# stm32.net
KiCad netlist of a schematic drawn in Altium Designer
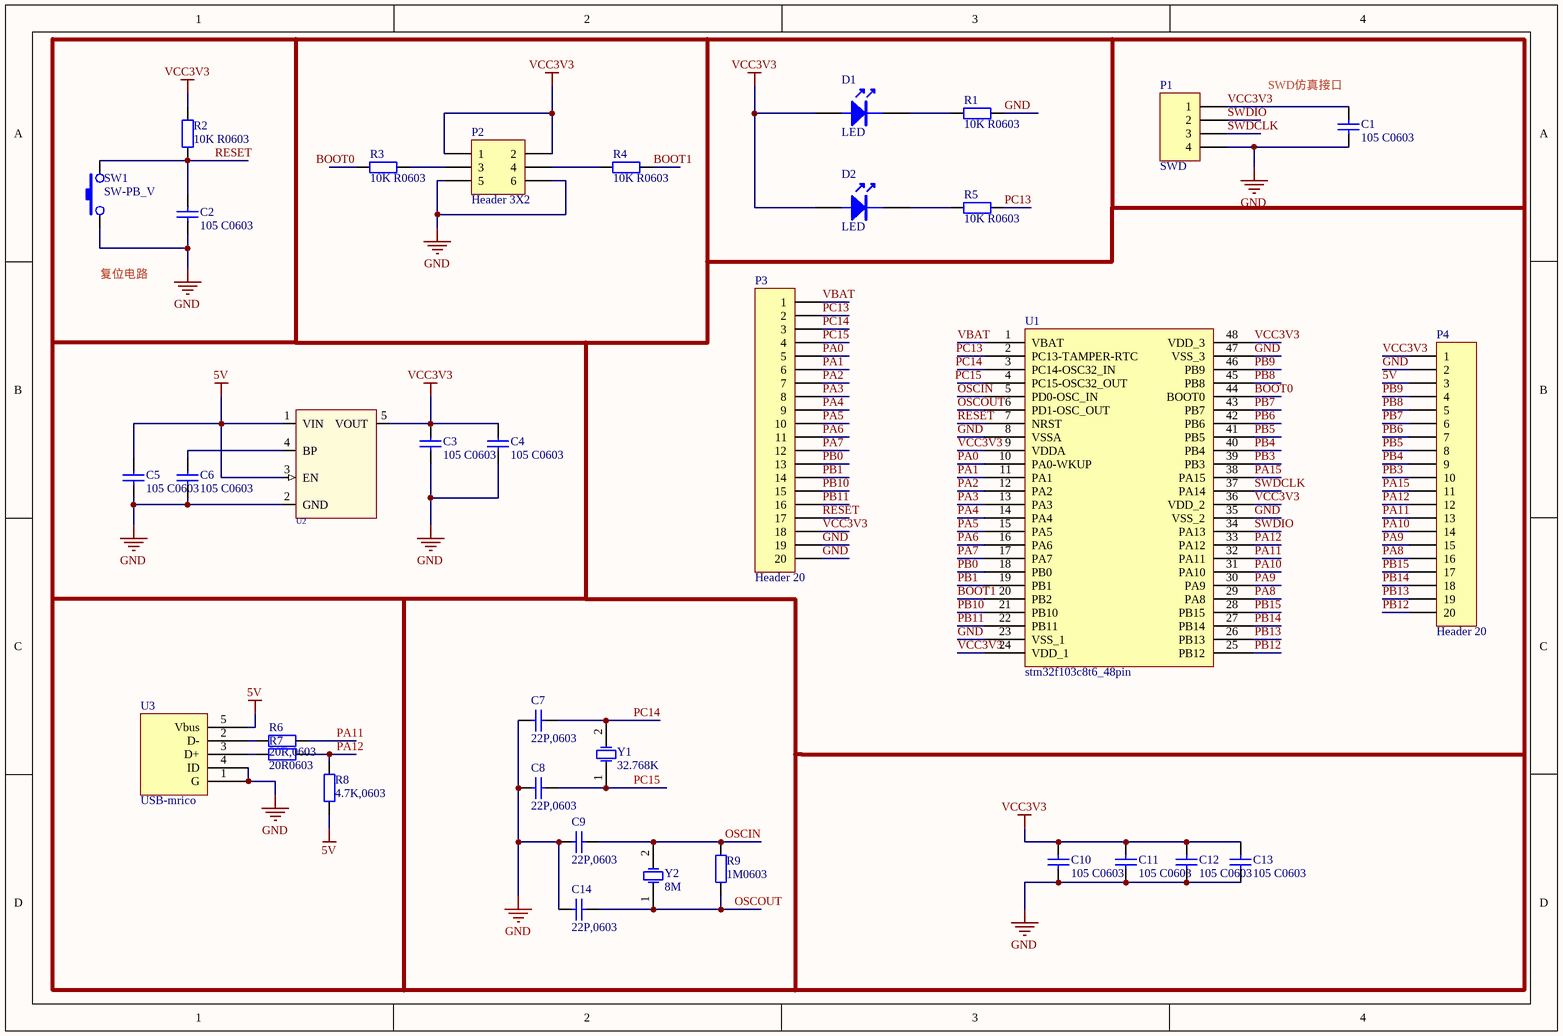
[diagram p0: stm32最小系统.SchDoc]

(export (version "E")
  (design (tool "Eeschema 10.0.6"))
  (components
    (comp (ref "C1")
      (value "105 C0603")
      (footprint "C 0603")
      (fields (field (name "PUBLISHER") "Altium Limited"))
      (libsource (lib "stm32原理图库") (part "Cap"))
    )
    (comp (ref "C2")
      (value "105 C0603")
      (footprint "C 0603")
      (fields (field (name "PUBLISHER") "Altium Limited"))
      (libsource (lib "stm32原理图库") (part "Cap"))
    )
    (comp (ref "C3")
      (value "105 C0603")
      (footprint "C 0603")
      (fields (field (name "PUBLISHER") "Altium Limited"))
      (libsource (lib "stm32原理图库") (part "Cap"))
    )
    (comp (ref "C4")
      (value "105 C0603")
      (footprint "C 0603")
      (fields (field (name "PUBLISHER") "Altium Limited"))
      (libsource (lib "stm32原理图库") (part "Cap"))
    )
    (comp (ref "C5")
      (value "105 C0603")
      (footprint "C 0603")
      (fields (field (name "PUBLISHER") "Altium Limited"))
      (libsource (lib "stm32原理图库") (part "Cap"))
    )
    (comp (ref "C6")
      (value "105 C0603")
      (footprint "C 0603")
      (fields (field (name "PUBLISHER") "Altium Limited"))
      (libsource (lib "stm32原理图库") (part "Cap"))
    )
    (comp (ref "C7")
      (value "22P,0603")
      (footprint "C 0603")
      (description "Capacitor")
      (fields (field (name "PUBLISHER") "Altium Limited"))
      (libsource (lib "STM32F103C8T6") (part "Cap"))
    )
    (comp (ref "C8")
      (value "22P,0603")
      (footprint "C 0603")
      (description "Capacitor")
      (fields (field (name "PUBLISHER") "Altium Limited"))
      (libsource (lib "STM32F103C8T6") (part "Cap"))
    )
    (comp (ref "C9")
      (value "22P,0603")
      (footprint "C 0603")
      (description "Capacitor")
      (fields (field (name "PUBLISHER") "Altium Limited"))
      (libsource (lib "STM32F103C8T6") (part "Cap"))
    )
    (comp (ref "C10")
      (value "105 C0603")
      (footprint "C 0603")
      (fields (field (name "PUBLISHER") "Altium Limited"))
      (libsource (lib "stm32原理图库") (part "Cap"))
    )
    (comp (ref "C11")
      (value "105 C0603")
      (footprint "C 0603")
      (fields (field (name "PUBLISHER") "Altium Limited"))
      (libsource (lib "stm32原理图库") (part "Cap"))
    )
    (comp (ref "C12")
      (value "105 C0603")
      (footprint "C 0603")
      (fields (field (name "PUBLISHER") "Altium Limited"))
      (libsource (lib "stm32原理图库") (part "Cap"))
    )
    (comp (ref "C13")
      (value "105 C0603")
      (footprint "C 0603")
      (fields (field (name "PUBLISHER") "Altium Limited"))
      (libsource (lib "stm32原理图库") (part "Cap"))
    )
    (comp (ref "C14")
      (value "22P,0603")
      (footprint "C 0603")
      (description "Capacitor")
      (fields (field (name "PUBLISHER") "Altium Limited"))
      (libsource (lib "STM32F103C8T6") (part "Cap"))
    )
    (comp (ref "D1") (value "LED") (footprint "LED 0805G") (libsource (lib "stm32原理图库") (part "LED")))
    (comp (ref "D2") (value "LED") (footprint "LED 0805G") (libsource (lib "stm32原理图库") (part "LED")))
    (comp (ref "P1")
      (value "SWD")
      (footprint "HDR-1X4_H")
      (description "Header, 4-Pin")
      (fields (field (name "PUBLISHER") "Altium Limited"))
      (libsource (lib "stm32原理图库") (part "Header 4"))
    )
    (comp (ref "P2")
      (value "Header 3X2")
      (footprint "HDR-3X2")
      (description "Header, 3-Pin, Dual row")
      (fields (field (name "PUBLISHER") "Altium Limited"))
      (libsource (lib "stm32原理图库") (part "Header 3X2"))
    )
    (comp (ref "P3")
      (value "Header 20")
      (footprint "HDR1X20")
      (description "Header, 20-Pin")
      (fields (field (name "PUBLISHER") "Altium Limited"))
      (libsource (lib "stm32原理图库") (part "Header 20"))
    )
    (comp (ref "P4")
      (value "Header 20")
      (footprint "HDR1X20")
      (description "Header, 20-Pin")
      (fields (field (name "PUBLISHER") "Altium Limited"))
      (libsource (lib "") (part "Header 20_1"))
    )
    (comp (ref "R1")
      (value "10K R0603")
      (footprint "R 0603")
      (fields (field (name "PUBLISHER") "Altium Limited"))
      (libsource (lib "stm32原理图库") (part "Res2"))
    )
    (comp (ref "R2")
      (value "10K R0603")
      (footprint "R 0603")
      (fields (field (name "PUBLISHER") "Altium Limited"))
      (libsource (lib "") (part "Res2_1"))
    )
    (comp (ref "R3")
      (value "10K R0603")
      (footprint "R 0603")
      (fields (field (name "PUBLISHER") "Altium Limited"))
      (libsource (lib "stm32原理图库") (part "Res2"))
    )
    (comp (ref "R4")
      (value "10K R0603")
      (footprint "R 0603")
      (fields (field (name "PUBLISHER") "Altium Limited"))
      (libsource (lib "stm32原理图库") (part "Res2"))
    )
    (comp (ref "R5")
      (value "10K R0603")
      (footprint "R 0603")
      (fields (field (name "PUBLISHER") "Altium Limited"))
      (libsource (lib "stm32原理图库") (part "Res2"))
    )
    (comp (ref "R6")
      (value "20R,0603")
      (footprint "R 0603")
      (description "Resistor")
      (fields (field (name "PUBLISHER") "Altium Limited"))
      (libsource (lib "") (part "Res2_1"))
    )
    (comp (ref "R7")
      (value "20R0603")
      (footprint "R 0603")
      (description "Resistor")
      (fields (field (name "PUBLISHER") "Altium Limited"))
      (libsource (lib "") (part "Res2_1"))
    )
    (comp (ref "R8")
      (value "4.7K,0603")
      (footprint "R 0603")
      (description "Resistor")
      (fields (field (name "PUBLISHER") "Altium Limited"))
      (libsource (lib "STM32F103C8T6") (part "Res2"))
    )
    (comp (ref "R9")
      (value "1M0603")
      (footprint "R 0603")
      (description "Resistor")
      (fields (field (name "PUBLISHER") "Altium Limited"))
      (libsource (lib "STM32F103C8T6") (part "Res2"))
    )
    (comp (ref "SW1")
      (value "SW-PB_V")
      (footprint "TSW SMD-3*6*2.5")
      (libsource (lib "stm32原理图库") (part "SW-PB_V"))
    )
    (comp (ref "U1")
      (value "stm32f103c8t6_48pin")
      (footprint "TQFP48 7x7_L")
      (libsource (lib "STM32_Schlib") (part "stm32f103c8t6_48pin"))
    )
    (comp (ref "U2")
      (value "RT9193")
      (footprint "SOT23-5L")
      (fields (field (name "ICA_PARTNUM") "$$2191094$$RT9193-15CU5") (field (name "PART NUMBER") "TMP-13"))
      (libsource (lib "stm32原理图库") (part "RT9193X_5P"))
    )
    (comp (ref "U3")
      (value "USB-mrico")
      (footprint "USB-micro_B")
      (libsource (lib "STM32F103C8T6") (part "usb-STM"))
    )
    (comp (ref "Y1")
      (value "32.768K")
      (footprint "XTAL-49S DIP")
      (description "Crystal Oscillator")
      (fields (field (name "PUBLISHER") "Altium Limited"))
      (libsource (lib "STM32F103C8T6") (part "XTAL"))
    )
    (comp (ref "Y2")
      (value "8M")
      (footprint "XTAL-49S DIP")
      (description "Crystal Oscillator")
      (fields (field (name "PUBLISHER") "Altium Limited"))
      (libsource (lib "STM32F103C8T6") (part "XTAL"))
    )
  )
  (nets
    (net (code "1") (name "/BOOT0") (class "Default")
      (node (ref "R3") (pin "1") (pinfunction "1_1") (pintype "passive"))
      (node (ref "U1") (pin "44") (pinfunction "BOOT0_44") (pintype "passive"))
    )
    (net (code "2") (name "/BOOT1") (class "Default")
      (node (ref "R4") (pin "2") (pinfunction "2_2") (pintype "passive"))
      (node (ref "U1") (pin "20") (pinfunction "PB2_20") (pintype "passive"))
    )
    (net (code "3") (name "/OSCIN") (class "Default")
      (node (ref "C9") (pin "1") (pinfunction "1_1") (pintype "passive"))
      (node (ref "R9") (pin "2") (pinfunction "2_2") (pintype "passive"))
      (node (ref "U1") (pin "5") (pinfunction "PD0-OSC_IN_5") (pintype "passive"))
      (node (ref "Y2") (pin "2") (pinfunction "OSC2_2") (pintype "passive"))
    )
    (net (code "4") (name "/OSCOUT") (class "Default")
      (node (ref "C14") (pin "1") (pinfunction "1_1") (pintype "passive"))
      (node (ref "R9") (pin "1") (pinfunction "1_1") (pintype "passive"))
      (node (ref "U1") (pin "6") (pinfunction "PD1-OSC_OUT_6") (pintype "passive"))
      (node (ref "Y2") (pin "1") (pinfunction "OSC1_1") (pintype "passive"))
    )
    (net (code "5") (name "/PA0") (class "Default")
      (node (ref "P3") (pin "5") (pinfunction "5_5") (pintype "passive"))
      (node (ref "U1") (pin "10") (pinfunction "PA0-WKUP_10") (pintype "passive"))
    )
    (net (code "6") (name "/PA1") (class "Default")
      (node (ref "P3") (pin "6") (pinfunction "6_6") (pintype "passive"))
      (node (ref "U1") (pin "11") (pinfunction "PA1_11") (pintype "passive"))
    )
    (net (code "7") (name "/PA2") (class "Default")
      (node (ref "P3") (pin "7") (pinfunction "7_7") (pintype "passive"))
      (node (ref "U1") (pin "12") (pinfunction "PA2_12") (pintype "passive"))
    )
    (net (code "8") (name "/PA3") (class "Default")
      (node (ref "P3") (pin "8") (pinfunction "8_8") (pintype "passive"))
      (node (ref "U1") (pin "13") (pinfunction "PA3_13") (pintype "passive"))
    )
    (net (code "9") (name "/PA4") (class "Default")
      (node (ref "P3") (pin "9") (pinfunction "9_9") (pintype "passive"))
      (node (ref "U1") (pin "14") (pinfunction "PA4_14") (pintype "passive"))
    )
    (net (code "10") (name "/PA5") (class "Default")
      (node (ref "P3") (pin "10") (pinfunction "10_10") (pintype "passive"))
      (node (ref "U1") (pin "15") (pinfunction "PA5_15") (pintype "passive"))
    )
    (net (code "11") (name "/PA6") (class "Default")
      (node (ref "P3") (pin "11") (pinfunction "11_11") (pintype "passive"))
      (node (ref "U1") (pin "16") (pinfunction "PA6_16") (pintype "passive"))
    )
    (net (code "12") (name "/PA7") (class "Default")
      (node (ref "P3") (pin "12") (pinfunction "12_12") (pintype "passive"))
      (node (ref "U1") (pin "17") (pinfunction "PA7_17") (pintype "passive"))
    )
    (net (code "13") (name "/PA8") (class "Default")
      (node (ref "P4") (pin "16") (pinfunction "16_16") (pintype "passive"))
      (node (ref "U1") (pin "29") (pinfunction "PA8_29") (pintype "passive"))
    )
    (net (code "14") (name "/PA9") (class "Default")
      (node (ref "P4") (pin "15") (pinfunction "15_15") (pintype "passive"))
      (node (ref "U1") (pin "30") (pinfunction "PA9_30") (pintype "passive"))
    )
    (net (code "15") (name "/PA10") (class "Default")
      (node (ref "P4") (pin "14") (pinfunction "14_14") (pintype "passive"))
      (node (ref "U1") (pin "31") (pinfunction "PA10_31") (pintype "passive"))
    )
    (net (code "16") (name "/PA11") (class "Default")
      (node (ref "P4") (pin "13") (pinfunction "13_13") (pintype "passive"))
      (node (ref "R6") (pin "2") (pinfunction "2_2") (pintype "passive"))
      (node (ref "U1") (pin "32") (pinfunction "PA11_32") (pintype "passive"))
    )
    (net (code "17") (name "/PA12") (class "Default")
      (node (ref "P4") (pin "12") (pinfunction "12_12") (pintype "passive"))
      (node (ref "R7") (pin "2") (pinfunction "2_2") (pintype "passive"))
      (node (ref "R8") (pin "2") (pinfunction "2_2") (pintype "passive"))
      (node (ref "U1") (pin "33") (pinfunction "PA12_33") (pintype "passive"))
    )
    (net (code "18") (name "/PA15") (class "Default")
      (node (ref "P4") (pin "11") (pinfunction "11_11") (pintype "passive"))
      (node (ref "U1") (pin "38") (pinfunction "PA15_38") (pintype "passive"))
    )
    (net (code "19") (name "/PB0") (class "Default")
      (node (ref "P3") (pin "13") (pinfunction "13_13") (pintype "passive"))
      (node (ref "U1") (pin "18") (pinfunction "PB0_18") (pintype "passive"))
    )
    (net (code "20") (name "/PB1") (class "Default")
      (node (ref "P3") (pin "14") (pinfunction "14_14") (pintype "passive"))
      (node (ref "U1") (pin "19") (pinfunction "PB1_19") (pintype "passive"))
    )
    (net (code "21") (name "/PB3") (class "Default")
      (node (ref "P4") (pin "10") (pinfunction "10_10") (pintype "passive"))
      (node (ref "U1") (pin "39") (pinfunction "PB3_39") (pintype "passive"))
    )
    (net (code "22") (name "/PB4") (class "Default")
      (node (ref "P4") (pin "9") (pinfunction "9_9") (pintype "passive"))
      (node (ref "U1") (pin "40") (pinfunction "PB4_40") (pintype "passive"))
    )
    (net (code "23") (name "/PB5") (class "Default")
      (node (ref "P4") (pin "8") (pinfunction "8_8") (pintype "passive"))
      (node (ref "U1") (pin "41") (pinfunction "PB5_41") (pintype "passive"))
    )
    (net (code "24") (name "/PB6") (class "Default")
      (node (ref "P4") (pin "7") (pinfunction "7_7") (pintype "passive"))
      (node (ref "U1") (pin "42") (pinfunction "PB6_42") (pintype "passive"))
    )
    (net (code "25") (name "/PB7") (class "Default")
      (node (ref "P4") (pin "6") (pinfunction "6_6") (pintype "passive"))
      (node (ref "U1") (pin "43") (pinfunction "PB7_43") (pintype "passive"))
    )
    (net (code "26") (name "/PB8") (class "Default")
      (node (ref "P4") (pin "5") (pinfunction "5_5") (pintype "passive"))
      (node (ref "U1") (pin "45") (pinfunction "PB8_45") (pintype "passive"))
    )
    (net (code "27") (name "/PB9") (class "Default")
      (node (ref "P4") (pin "4") (pinfunction "4_4") (pintype "passive"))
      (node (ref "U1") (pin "46") (pinfunction "PB9_46") (pintype "passive"))
    )
    (net (code "28") (name "/PB10") (class "Default")
      (node (ref "P3") (pin "15") (pinfunction "15_15") (pintype "passive"))
      (node (ref "U1") (pin "21") (pinfunction "PB10_21") (pintype "passive"))
    )
    (net (code "29") (name "/PB11") (class "Default")
      (node (ref "P3") (pin "16") (pinfunction "16_16") (pintype "passive"))
      (node (ref "U1") (pin "22") (pinfunction "PB11_22") (pintype "passive"))
    )
    (net (code "30") (name "/PB12") (class "Default")
      (node (ref "P4") (pin "20") (pinfunction "20_20") (pintype "passive"))
      (node (ref "U1") (pin "25") (pinfunction "PB12_25") (pintype "passive"))
    )
    (net (code "31") (name "/PB13") (class "Default")
      (node (ref "P4") (pin "19") (pinfunction "19_19") (pintype "passive"))
      (node (ref "U1") (pin "26") (pinfunction "PB13_26") (pintype "passive"))
    )
    (net (code "32") (name "/PB14") (class "Default")
      (node (ref "P4") (pin "18") (pinfunction "18_18") (pintype "passive"))
      (node (ref "U1") (pin "27") (pinfunction "PB14_27") (pintype "passive"))
    )
    (net (code "33") (name "/PB15") (class "Default")
      (node (ref "P4") (pin "17") (pinfunction "17_17") (pintype "passive"))
      (node (ref "U1") (pin "28") (pinfunction "PB15_28") (pintype "passive"))
    )
    (net (code "34") (name "/PC13") (class "Default")
      (node (ref "P3") (pin "2") (pinfunction "2_2") (pintype "passive"))
      (node (ref "R5") (pin "2") (pinfunction "2_2") (pintype "passive"))
      (node (ref "U1") (pin "2") (pinfunction "PC13-TAMPER-RTC_2") (pintype "passive"))
    )
    (net (code "35") (name "/PC14") (class "Default")
      (node (ref "C7") (pin "1") (pinfunction "1_1") (pintype "passive"))
      (node (ref "P3") (pin "3") (pinfunction "3_3") (pintype "passive"))
      (node (ref "U1") (pin "3") (pinfunction "PC14-OSC32_IN_3") (pintype "passive"))
      (node (ref "Y1") (pin "2") (pinfunction "OSC2_2") (pintype "passive"))
    )
    (net (code "36") (name "/PC15") (class "Default")
      (node (ref "C8") (pin "1") (pinfunction "1_1") (pintype "passive"))
      (node (ref "P3") (pin "4") (pinfunction "4_4") (pintype "passive"))
      (node (ref "U1") (pin "4") (pinfunction "PC15-OSC32_OUT_4") (pintype "passive"))
      (node (ref "Y1") (pin "1") (pinfunction "OSC1_1") (pintype "passive"))
    )
    (net (code "37") (name "/RESET") (class "Default")
      (node (ref "C2") (pin "2") (pinfunction "2_2") (pintype "passive"))
      (node (ref "P3") (pin "17") (pinfunction "17_17") (pintype "passive"))
      (node (ref "R2") (pin "1") (pinfunction "1_1") (pintype "passive"))
      (node (ref "SW1") (pin "2") (pinfunction "2_2") (pintype "passive"))
      (node (ref "U1") (pin "7") (pinfunction "NRST_7") (pintype "passive"))
    )
    (net (code "38") (name "/SWDCLK") (class "Default")
      (node (ref "P1") (pin "3") (pinfunction "3_3") (pintype "passive"))
      (node (ref "U1") (pin "37") (pinfunction "PA14_37") (pintype "passive"))
    )
    (net (code "39") (name "/SWDIO") (class "Default")
      (node (ref "P1") (pin "2") (pinfunction "2_2") (pintype "passive"))
      (node (ref "U1") (pin "34") (pinfunction "PA13_34") (pintype "passive"))
    )
    (net (code "40") (name "/VBAT") (class "Default")
      (node (ref "P3") (pin "1") (pinfunction "1_1") (pintype "passive"))
      (node (ref "U1") (pin "1") (pinfunction "VBAT_1") (pintype "passive"))
    )
    (net (code "41") (name "5V") (class "Default")
      (node (ref "C5") (pin "2") (pinfunction "2_2") (pintype "passive"))
      (node (ref "P4") (pin "3") (pinfunction "3_3") (pintype "passive"))
      (node (ref "R8") (pin "1") (pinfunction "1_1") (pintype "passive"))
      (node (ref "U2") (pin "1") (pinfunction "VIN_1") (pintype "power_in"))
      (node (ref "U2") (pin "3") (pinfunction "EN_3") (pintype "input"))
      (node (ref "U3") (pin "5") (pinfunction "Vbus_5") (pintype "passive"))
    )
    (net (code "42") (name "GND") (class "Default")
      (node (ref "C1") (pin "1") (pinfunction "1_1") (pintype "passive"))
      (node (ref "C10") (pin "1") (pinfunction "1_1") (pintype "passive"))
      (node (ref "C11") (pin "1") (pinfunction "1_1") (pintype "passive"))
      (node (ref "C12") (pin "1") (pinfunction "1_1") (pintype "passive"))
      (node (ref "C13") (pin "1") (pinfunction "1_1") (pintype "passive"))
      (node (ref "C14") (pin "2") (pinfunction "2_2") (pintype "passive"))
      (node (ref "C2") (pin "1") (pinfunction "1_1") (pintype "passive"))
      (node (ref "C3") (pin "1") (pinfunction "1_1") (pintype "passive"))
      (node (ref "C4") (pin "1") (pinfunction "1_1") (pintype "passive"))
      (node (ref "C5") (pin "1") (pinfunction "1_1") (pintype "passive"))
      (node (ref "C6") (pin "1") (pinfunction "1_1") (pintype "passive"))
      (node (ref "C7") (pin "2") (pinfunction "2_2") (pintype "passive"))
      (node (ref "C8") (pin "2") (pinfunction "2_2") (pintype "passive"))
      (node (ref "C9") (pin "2") (pinfunction "2_2") (pintype "passive"))
      (node (ref "P1") (pin "4") (pinfunction "4_4") (pintype "passive"))
      (node (ref "P2") (pin "5") (pinfunction "5_5") (pintype "passive"))
      (node (ref "P2") (pin "6") (pinfunction "6_6") (pintype "passive"))
      (node (ref "P3") (pin "19") (pinfunction "19_19") (pintype "passive"))
      (node (ref "P3") (pin "20") (pinfunction "20_20") (pintype "passive"))
      (node (ref "P4") (pin "2") (pinfunction "2_2") (pintype "passive"))
      (node (ref "R1") (pin "2") (pinfunction "2_2") (pintype "passive"))
      (node (ref "SW1") (pin "1") (pinfunction "1_1") (pintype "passive"))
      (node (ref "U1") (pin "23") (pinfunction "VSS_1_23") (pintype "passive"))
      (node (ref "U1") (pin "35") (pinfunction "VSS_2_35") (pintype "passive"))
      (node (ref "U1") (pin "47") (pinfunction "VSS_3_47") (pintype "passive"))
      (node (ref "U1") (pin "8") (pinfunction "VSSA_8") (pintype "passive"))
      (node (ref "U2") (pin "2") (pinfunction "GND_2") (pintype "power_in"))
      (node (ref "U3") (pin "1") (pinfunction "G_1") (pintype "passive"))
      (node (ref "U3") (pin "4") (pinfunction "ID_4") (pintype "passive"))
    )
    (net (code "43") (name "Net-(D1-Pad2)") (class "Default")
      (node (ref "D1") (pin "2") (pinfunction "2_2") (pintype "passive"))
      (node (ref "R1") (pin "1") (pinfunction "1_1") (pintype "passive"))
    )
    (net (code "44") (name "Net-(D2-Pad2)") (class "Default")
      (node (ref "D2") (pin "2") (pinfunction "2_2") (pintype "passive"))
      (node (ref "R5") (pin "1") (pinfunction "1_1") (pintype "passive"))
    )
    (net (code "45") (name "Net-(P2-Pad3)") (class "Default")
      (node (ref "P2") (pin "3") (pinfunction "3_3") (pintype "passive"))
      (node (ref "R3") (pin "2") (pinfunction "2_2") (pintype "passive"))
    )
    (net (code "46") (name "Net-(P2-Pad4)") (class "Default")
      (node (ref "P2") (pin "4") (pinfunction "4_4") (pintype "passive"))
      (node (ref "R4") (pin "1") (pinfunction "1_1") (pintype "passive"))
    )
    (net (code "47") (name "Net-(U2-BP)") (class "Default")
      (node (ref "C6") (pin "2") (pinfunction "2_2") (pintype "passive"))
      (node (ref "U2") (pin "4") (pinfunction "BP_4") (pintype "passive"))
    )
    (net (code "48") (name "Net-(U3-D+)") (class "Default")
      (node (ref "R7") (pin "1") (pinfunction "1_1") (pintype "passive"))
      (node (ref "U3") (pin "3") (pinfunction "D+_3") (pintype "passive"))
    )
    (net (code "49") (name "Net-(U3-D-)") (class "Default")
      (node (ref "R6") (pin "1") (pinfunction "1_1") (pintype "passive"))
      (node (ref "U3") (pin "2") (pinfunction "D-_2") (pintype "passive"))
    )
    (net (code "50") (name "VCC3V3") (class "Default")
      (node (ref "C1") (pin "2") (pinfunction "2_2") (pintype "passive"))
      (node (ref "C10") (pin "2") (pinfunction "2_2") (pintype "passive"))
      (node (ref "C11") (pin "2") (pinfunction "2_2") (pintype "passive"))
      (node (ref "C12") (pin "2") (pinfunction "2_2") (pintype "passive"))
      (node (ref "C13") (pin "2") (pinfunction "2_2") (pintype "passive"))
      (node (ref "C3") (pin "2") (pinfunction "2_2") (pintype "passive"))
      (node (ref "C4") (pin "2") (pinfunction "2_2") (pintype "passive"))
      (node (ref "D1") (pin "1") (pinfunction "1_1") (pintype "passive"))
      (node (ref "D2") (pin "1") (pinfunction "1_1") (pintype "passive"))
      (node (ref "P1") (pin "1") (pinfunction "1_1") (pintype "passive"))
      (node (ref "P2") (pin "1") (pinfunction "1_1") (pintype "passive"))
      (node (ref "P2") (pin "2") (pinfunction "2_2") (pintype "passive"))
      (node (ref "P3") (pin "18") (pinfunction "18_18") (pintype "passive"))
      (node (ref "P4") (pin "1") (pinfunction "1_1") (pintype "passive"))
      (node (ref "R2") (pin "2") (pinfunction "2_2") (pintype "passive"))
      (node (ref "U1") (pin "24") (pinfunction "VDD_1_24") (pintype "passive"))
      (node (ref "U1") (pin "36") (pinfunction "VDD_2_36") (pintype "passive"))
      (node (ref "U1") (pin "48") (pinfunction "VDD_3_48") (pintype "passive"))
      (node (ref "U1") (pin "9") (pinfunction "VDDA_9") (pintype "passive"))
      (node (ref "U2") (pin "5") (pinfunction "VOUT_5") (pintype "power_in"))
    )
  )
)
